# LIC_rack_CV-00.net
KiCad netlist of a schematic drawn in EAGLE
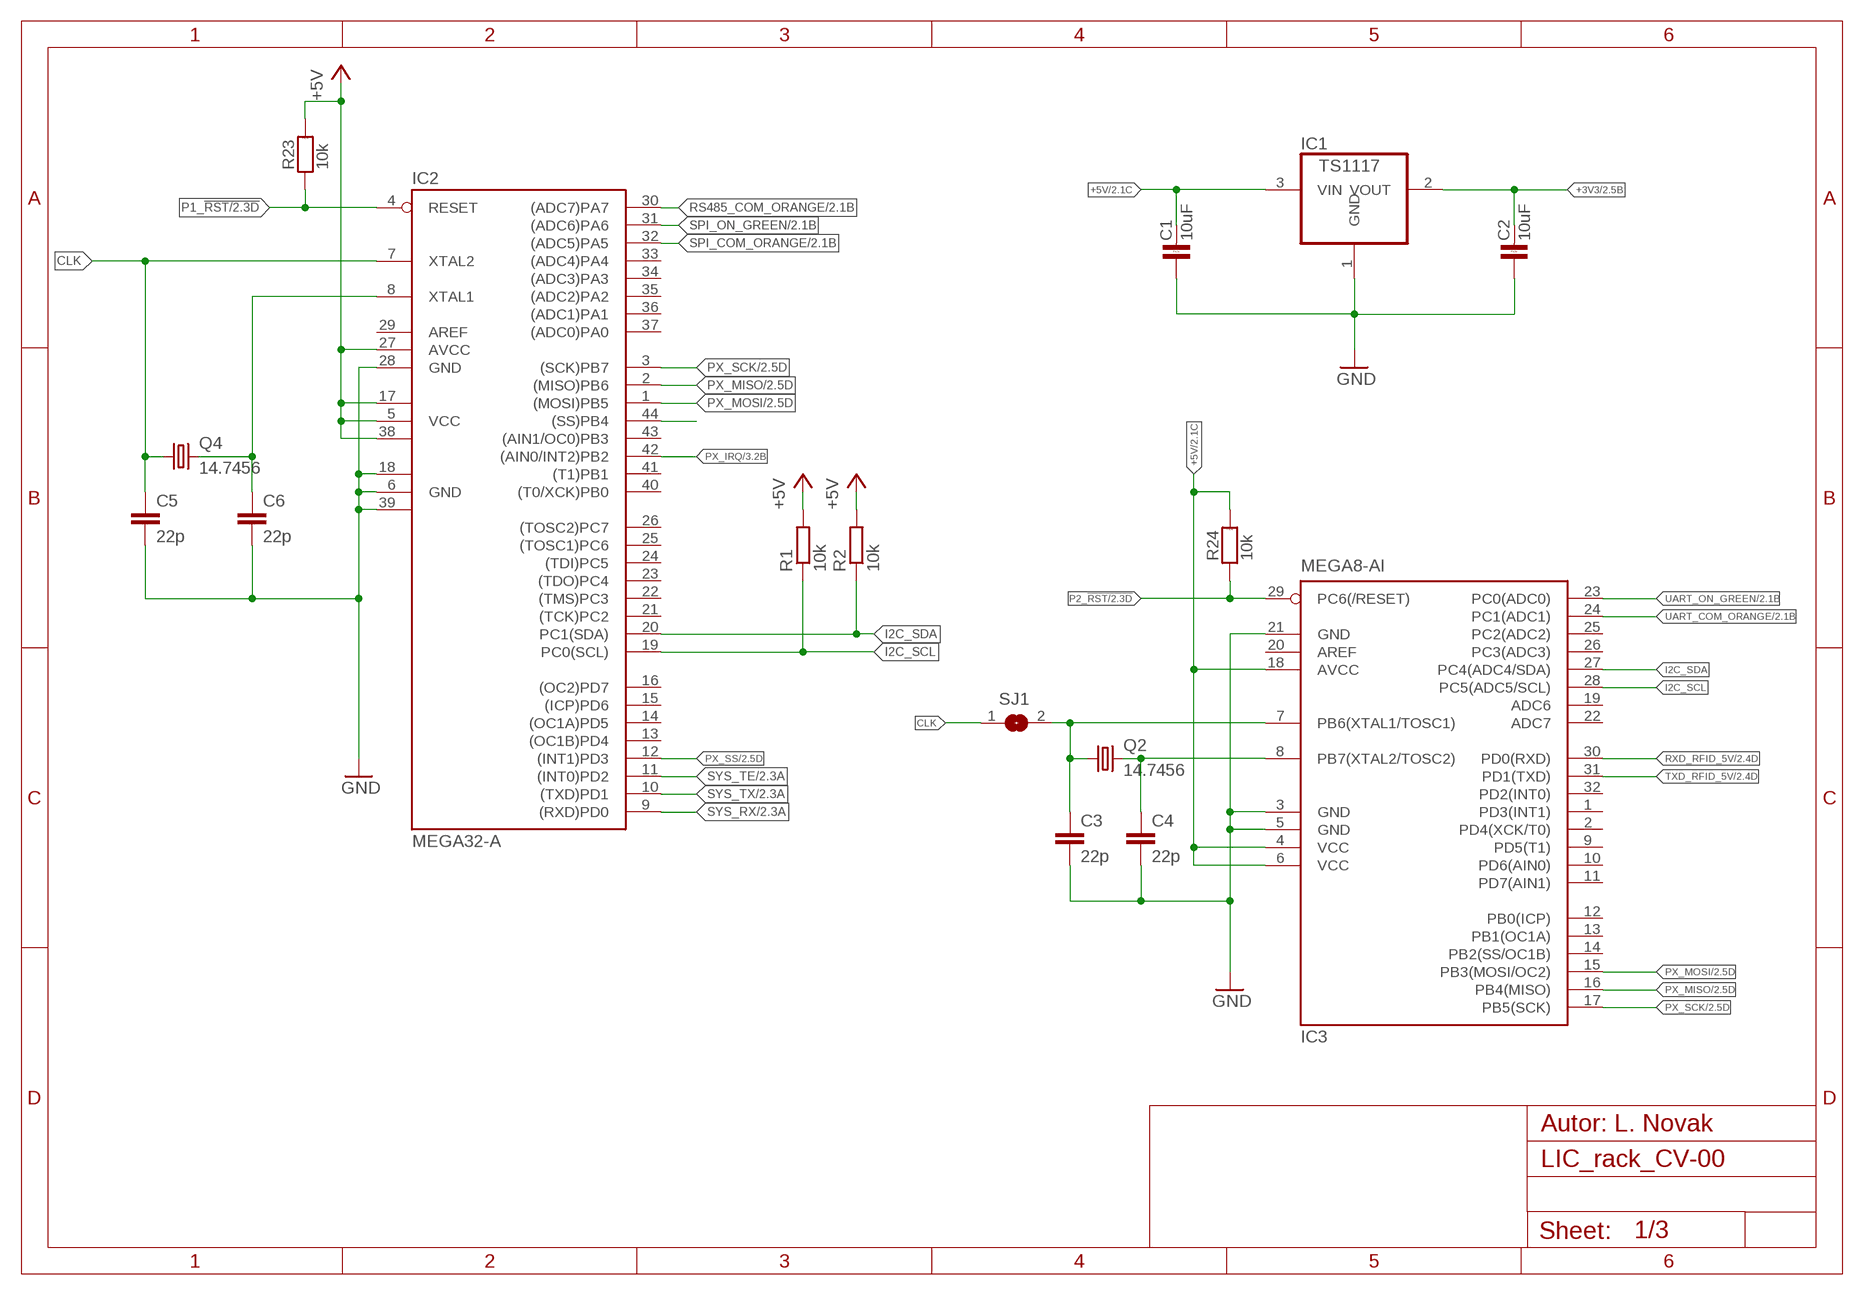
[diagram p0: schematic, sheet 1]
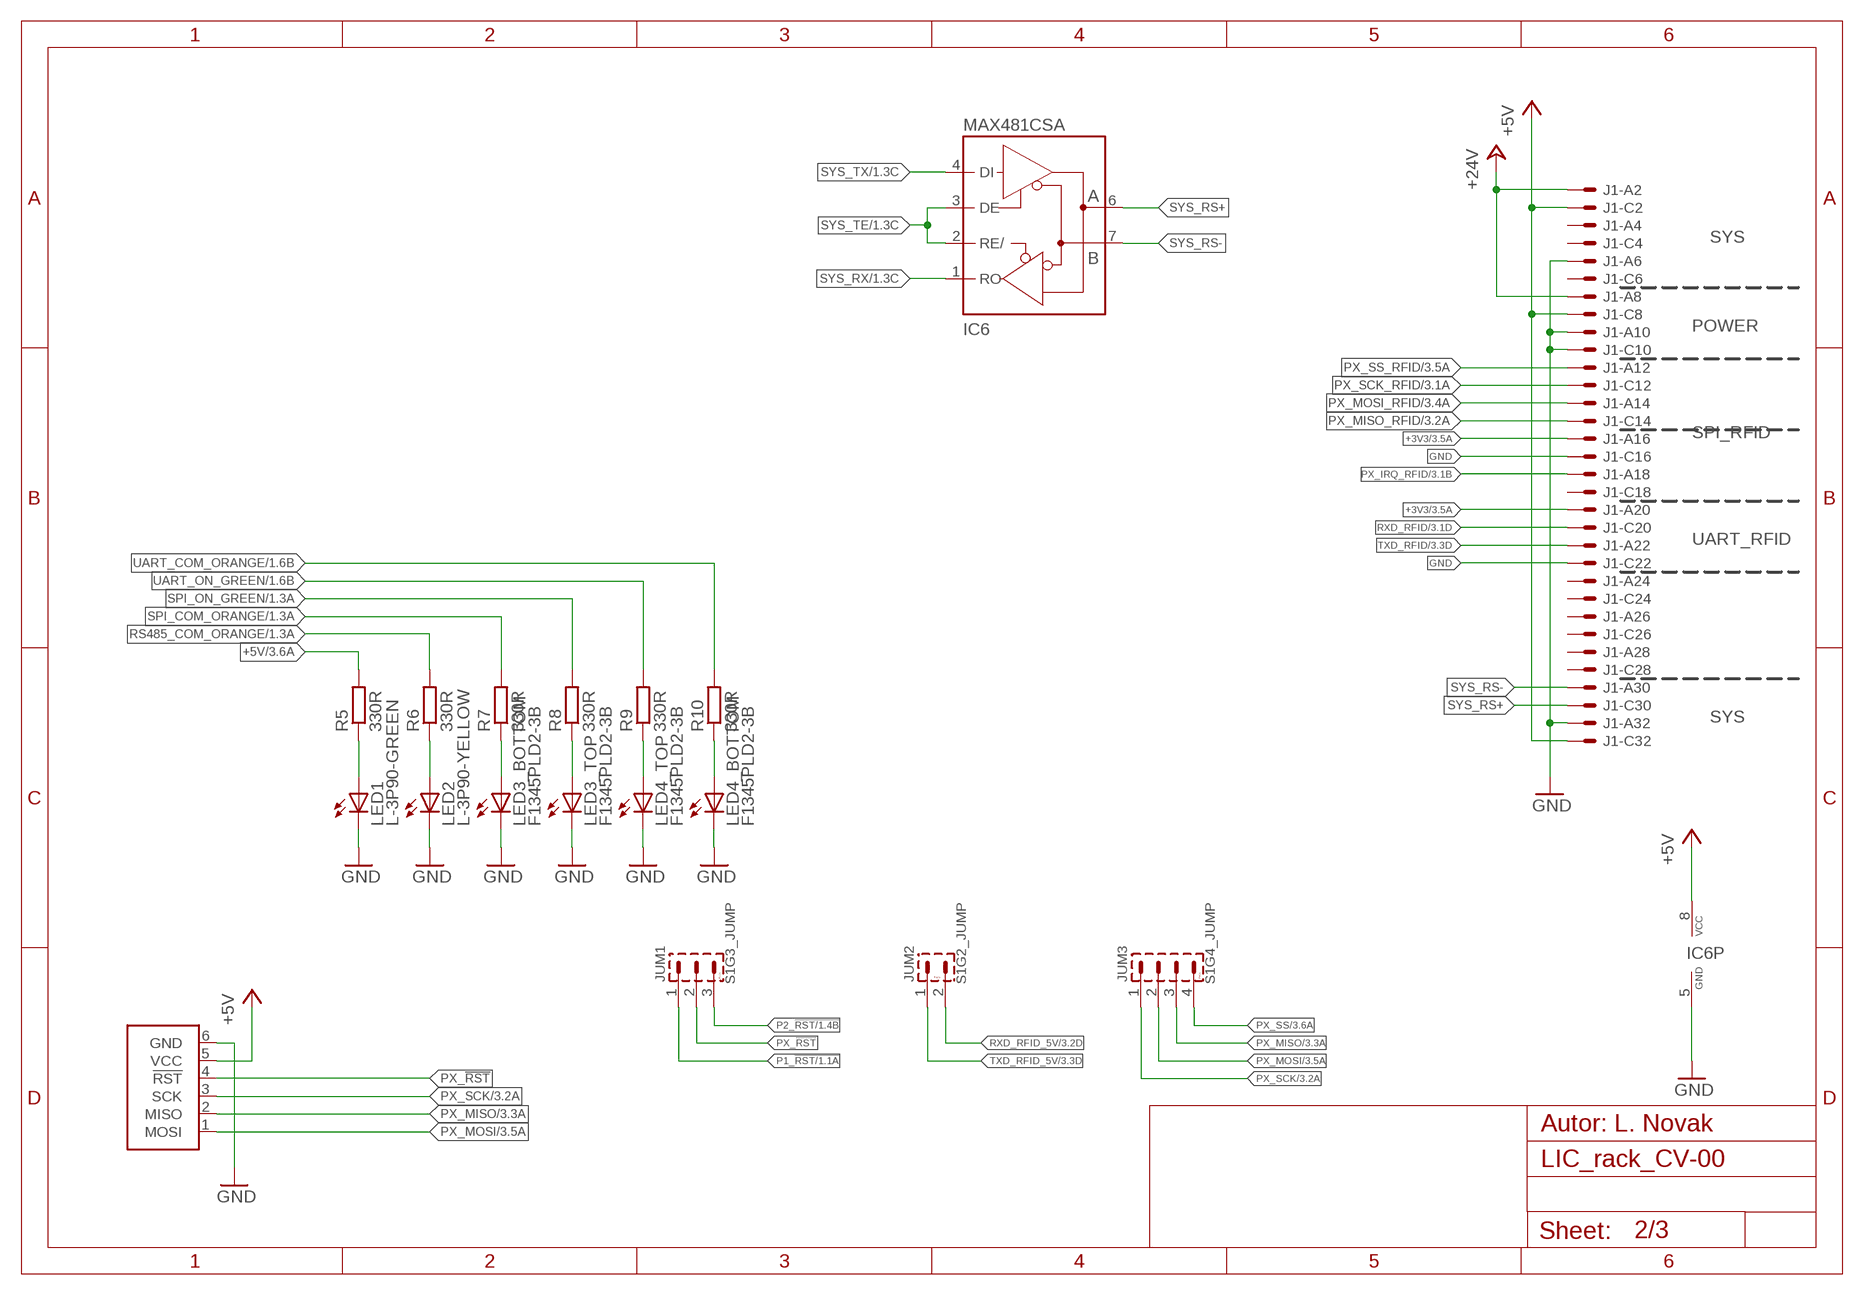
[diagram p1: schematic, sheet 2]
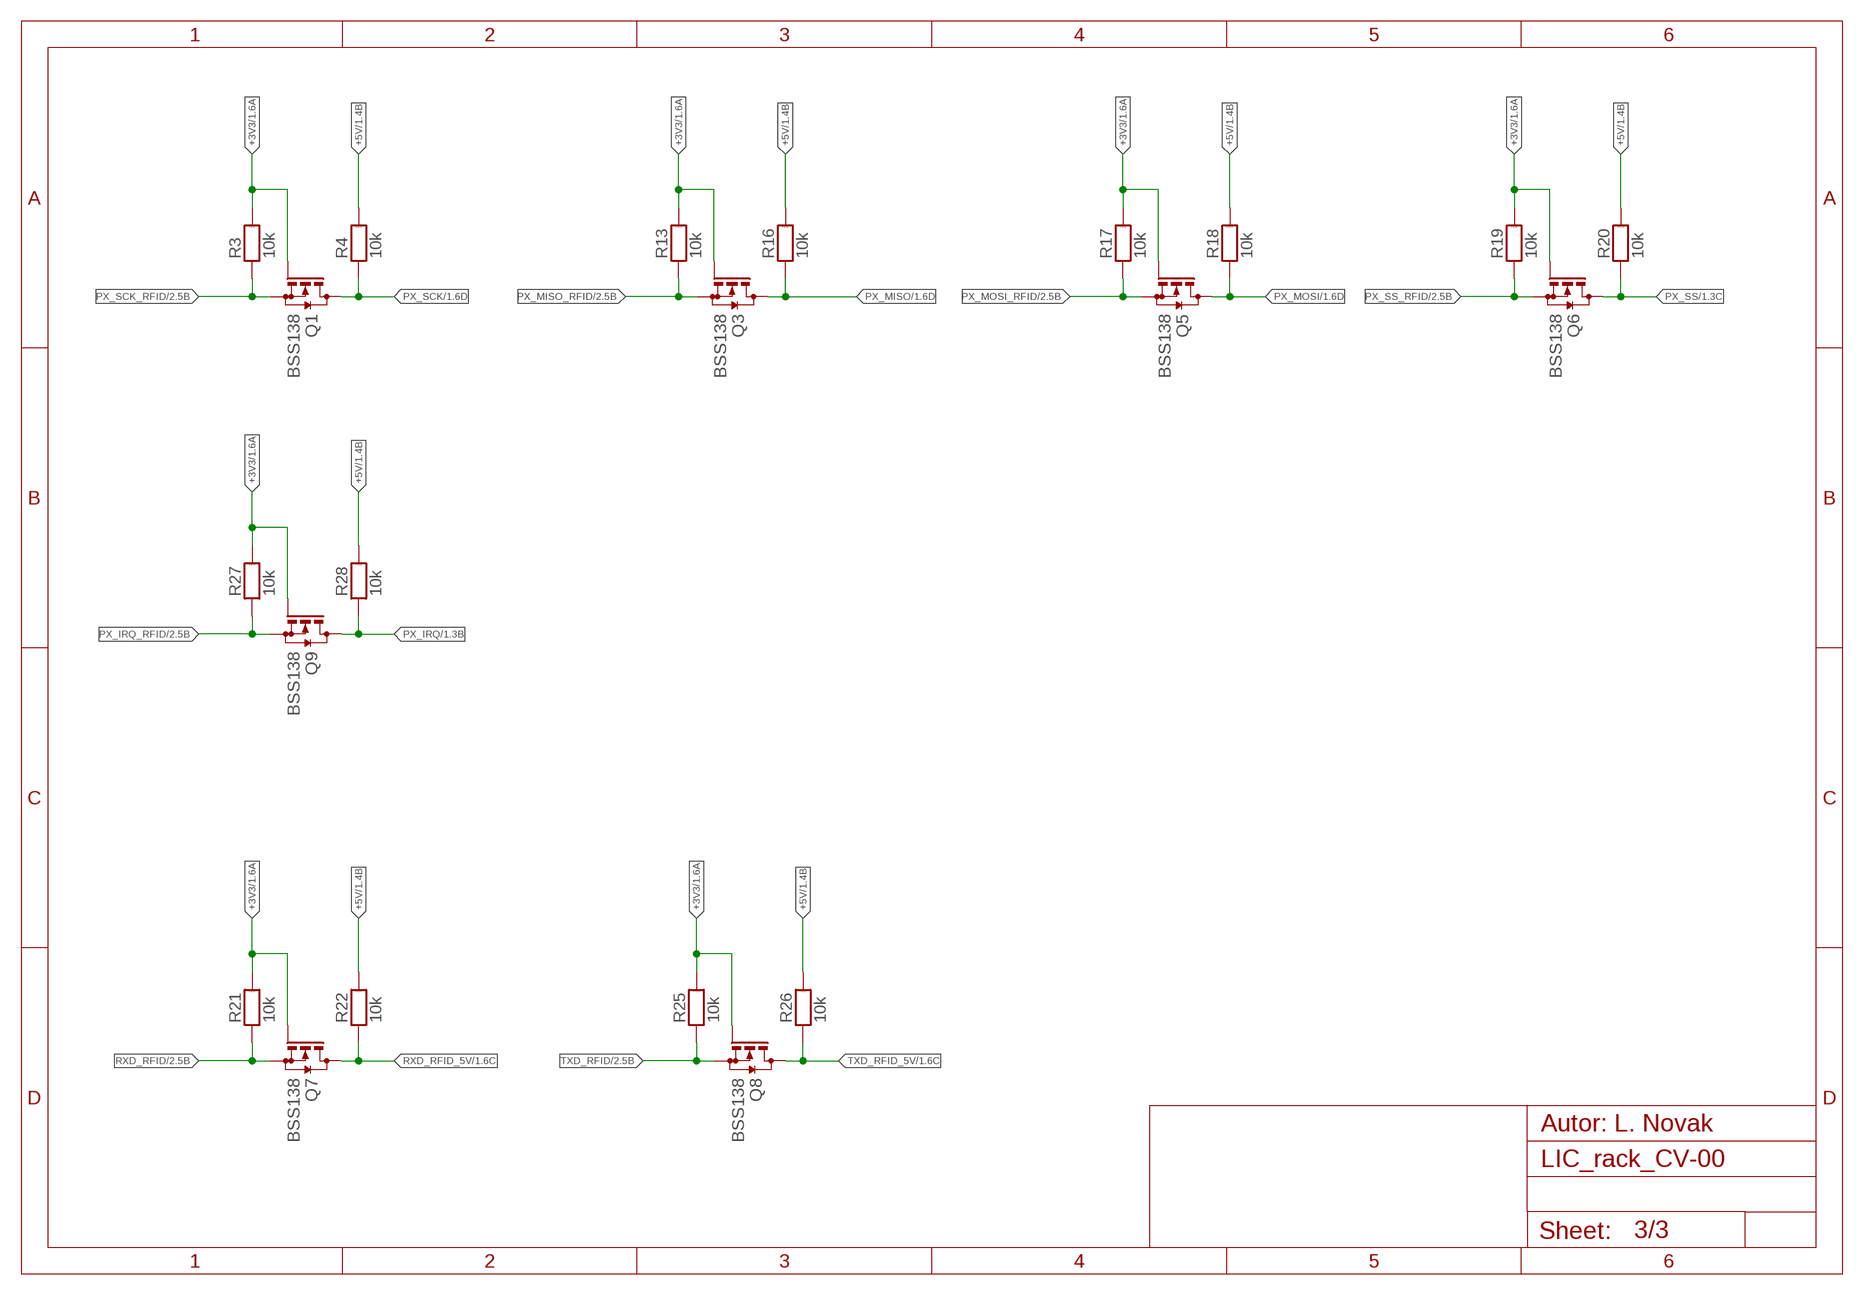
[diagram p2: schematic, sheet 3]

(export (version "E")
  (design (tool "Eeschema 10.0.6"))
  (components
    (comp (ref "IC6")
      (value "MAX481CSA")
      (footprint "eagle-import:SO08")
      (libsource (lib "eagle-import") (part "MAX481CSA"))
    )
    (comp (ref "J1")
      (value "VG32SP")
      (footprint "eagle-import:VG32P")
      (libsource (lib "eagle-import") (part "VG32SP"))
    )
    (comp (ref "JUM1")
      (value "S1G3_JUMP")
      (footprint "eagle-import:S1G3_JUM")
      (libsource (lib "eagle-import") (part "S1G3_JUMP"))
    )
    (comp (ref "JUM2")
      (value "S1G2_JUMP")
      (footprint "eagle-import:S1G2_JUM")
      (libsource (lib "eagle-import") (part "S1G2_JUMP"))
    )
    (comp (ref "JUM3")
      (value "S1G4_JUMP")
      (footprint "eagle-import:S1G4_JUM")
      (libsource (lib "eagle-import") (part "S1G4_JUMP"))
    )
    (comp (ref "LED1")
      (value "L-3P90-GREEN")
      (footprint "eagle-import:L-3P90")
      (libsource (lib "eagle-import") (part "L-3P90-GREEN"))
    )
    (comp (ref "LED2")
      (value "L-3P90-YELLOW")
      (footprint "eagle-import:L-3P90")
      (libsource (lib "eagle-import") (part "L-3P90-YELLOW"))
    )
    (comp (ref "LED3")
      (value "F1345PLD2-3B")
      (footprint "eagle-import:F1345PLD2-3B")
      (libsource (lib "eagle-import") (part "F1345PLD2-3B"))
    )
    (comp (ref "LED4")
      (value "F1345PLD2-3B")
      (footprint "eagle-import:F1345PLD2-3B")
      (libsource (lib "eagle-import") (part "F1345PLD2-3B"))
    )
    (comp (ref "R5")
      (value "330R")
      (footprint "eagle-import:R1206")
      (libsource (lib "eagle-import") (part "R-EU_R1206"))
    )
    (comp (ref "R6")
      (value "330R")
      (footprint "eagle-import:R1206")
      (libsource (lib "eagle-import") (part "R-EU_R1206"))
    )
    (comp (ref "R7")
      (value "330R")
      (footprint "eagle-import:R1206")
      (libsource (lib "eagle-import") (part "R-EU_R1206"))
    )
    (comp (ref "R8")
      (value "330R")
      (footprint "eagle-import:R1206")
      (libsource (lib "eagle-import") (part "R-EU_R1206"))
    )
    (comp (ref "R9")
      (value "330R")
      (footprint "eagle-import:R1206")
      (libsource (lib "eagle-import") (part "R-EU_R1206"))
    )
    (comp (ref "R10")
      (value "330R")
      (footprint "eagle-import:R1206")
      (libsource (lib "eagle-import") (part "R-EU_R1206"))
    )
    (comp (ref "U1")
      (value "ATPROG-V")
      (footprint "eagle-import:6410-06")
      (libsource (lib "eagle-import") (part "ATPROG-V"))
    )
    (comp (ref "Q1")
      (value "BSS138")
      (footprint "eagle-import:SOT23")
      (libsource (lib "eagle-import") (part "BSS123"))
    )
    (comp (ref "Q3")
      (value "BSS138")
      (footprint "eagle-import:SOT23")
      (libsource (lib "eagle-import") (part "BSS123"))
    )
    (comp (ref "Q5")
      (value "BSS138")
      (footprint "eagle-import:SOT23")
      (libsource (lib "eagle-import") (part "BSS123"))
    )
    (comp (ref "Q6")
      (value "BSS138")
      (footprint "eagle-import:SOT23")
      (libsource (lib "eagle-import") (part "BSS123"))
    )
    (comp (ref "Q7")
      (value "BSS138")
      (footprint "eagle-import:SOT23")
      (libsource (lib "eagle-import") (part "BSS123"))
    )
    (comp (ref "Q8")
      (value "BSS138")
      (footprint "eagle-import:SOT23")
      (libsource (lib "eagle-import") (part "BSS123"))
    )
    (comp (ref "Q9")
      (value "BSS138")
      (footprint "eagle-import:SOT23")
      (libsource (lib "eagle-import") (part "BSS123"))
    )
    (comp (ref "R3")
      (value "10k")
      (footprint "eagle-import:1206")
      (libsource (lib "eagle-import") (part "R_1206"))
    )
    (comp (ref "R4")
      (value "10k")
      (footprint "eagle-import:1206")
      (libsource (lib "eagle-import") (part "R_1206"))
    )
    (comp (ref "R13")
      (value "10k")
      (footprint "eagle-import:1206")
      (libsource (lib "eagle-import") (part "R_1206"))
    )
    (comp (ref "R16")
      (value "10k")
      (footprint "eagle-import:1206")
      (libsource (lib "eagle-import") (part "R_1206"))
    )
    (comp (ref "R17")
      (value "10k")
      (footprint "eagle-import:1206")
      (libsource (lib "eagle-import") (part "R_1206"))
    )
    (comp (ref "R18")
      (value "10k")
      (footprint "eagle-import:1206")
      (libsource (lib "eagle-import") (part "R_1206"))
    )
    (comp (ref "R19")
      (value "10k")
      (footprint "eagle-import:1206")
      (libsource (lib "eagle-import") (part "R_1206"))
    )
    (comp (ref "R20")
      (value "10k")
      (footprint "eagle-import:1206")
      (libsource (lib "eagle-import") (part "R_1206"))
    )
    (comp (ref "R21")
      (value "10k")
      (footprint "eagle-import:1206")
      (libsource (lib "eagle-import") (part "R_1206"))
    )
    (comp (ref "R22")
      (value "10k")
      (footprint "eagle-import:1206")
      (libsource (lib "eagle-import") (part "R_1206"))
    )
    (comp (ref "R25")
      (value "10k")
      (footprint "eagle-import:1206")
      (libsource (lib "eagle-import") (part "R_1206"))
    )
    (comp (ref "R26")
      (value "10k")
      (footprint "eagle-import:1206")
      (libsource (lib "eagle-import") (part "R_1206"))
    )
    (comp (ref "R27")
      (value "10k")
      (footprint "eagle-import:1206")
      (libsource (lib "eagle-import") (part "R_1206"))
    )
    (comp (ref "R28")
      (value "10k")
      (footprint "eagle-import:1206")
      (libsource (lib "eagle-import") (part "R_1206"))
    )
    (comp (ref "C1")
      (value "10uF")
      (footprint "eagle-import:1206")
      (libsource (lib "eagle-import") (part "C-KER_1206"))
    )
    (comp (ref "C2")
      (value "10uF")
      (footprint "eagle-import:1206")
      (libsource (lib "eagle-import") (part "C-KER_1206"))
    )
    (comp (ref "C3")
      (value "22p")
      (footprint "eagle-import:C0805")
      (libsource (lib "eagle-import") (part "C-EUC0805"))
    )
    (comp (ref "C4")
      (value "22p")
      (footprint "eagle-import:C0805")
      (libsource (lib "eagle-import") (part "C-EUC0805"))
    )
    (comp (ref "C5")
      (value "22p")
      (footprint "eagle-import:C0805")
      (libsource (lib "eagle-import") (part "C-EUC0805"))
    )
    (comp (ref "C6")
      (value "22p")
      (footprint "eagle-import:C0805")
      (libsource (lib "eagle-import") (part "C-EUC0805"))
    )
    (comp (ref "IC1")
      (value "TS1117")
      (footprint "eagle-import:SOT223")
      (fields (field (name "MPN") "REG1117"))
      (libsource (lib "eagle-import") (part "REG1117"))
    )
    (comp (ref "IC2")
      (value "MEGA32-A")
      (footprint "eagle-import:TQFP44")
      (fields (field (name "MPN") "ATMEGA32-16AU"))
      (libsource (lib "eagle-import") (part "MEGA32-A"))
    )
    (comp (ref "IC3")
      (value "MEGA8-AI")
      (footprint "eagle-import:TQFP32-08")
      (fields (field (name "MPN") "ATMEGA8-16AU"))
      (libsource (lib "eagle-import") (part "MEGA8-AI"))
    )
    (comp (ref "Q2")
      (value "14.7456")
      (footprint "eagle-import:HC49U70")
      (libsource (lib "eagle-import") (part "XTAL"))
    )
    (comp (ref "Q4")
      (value "14.7456")
      (footprint "eagle-import:HC49U70")
      (libsource (lib "eagle-import") (part "XTAL"))
    )
    (comp (ref "R1")
      (value "10k")
      (footprint "eagle-import:R1206")
      (libsource (lib "eagle-import") (part "R-EU_R1206"))
    )
    (comp (ref "R2")
      (value "10k")
      (footprint "eagle-import:R1206")
      (libsource (lib "eagle-import") (part "R-EU_R1206"))
    )
    (comp (ref "R23")
      (value "10k")
      (footprint "eagle-import:1206")
      (libsource (lib "eagle-import") (part "R_1206"))
    )
    (comp (ref "R24")
      (value "10k")
      (footprint "eagle-import:1206")
      (libsource (lib "eagle-import") (part "R_1206"))
    )
    (comp (ref "SJ1") (value "SJ") (footprint "eagle-import:SJ") (libsource (lib "eagle-import") (part "SJ")))
  )
  (nets
    (net (code "1") (name "+3V3") (class "Default")
      (node (ref "C2") (pin "2") (pinfunction "2_2") (pintype "passive"))
      (node (ref "IC1") (pin "2") (pinfunction "VOUT_2") (pintype "output"))
      (node (ref "J1") (pin "A16") (pinfunction "MS_A16") (pintype "passive"))
      (node (ref "J1") (pin "A20") (pinfunction "MS_A20") (pintype "passive"))
      (node (ref "Q1") (pin "1") (pinfunction "G_1") (pintype "passive"))
      (node (ref "Q3") (pin "1") (pinfunction "G_1") (pintype "passive"))
      (node (ref "Q5") (pin "1") (pinfunction "G_1") (pintype "passive"))
      (node (ref "Q6") (pin "1") (pinfunction "G_1") (pintype "passive"))
      (node (ref "Q7") (pin "1") (pinfunction "G_1") (pintype "passive"))
      (node (ref "Q8") (pin "1") (pinfunction "G_1") (pintype "passive"))
      (node (ref "Q9") (pin "1") (pinfunction "G_1") (pintype "passive"))
      (node (ref "R13") (pin "2") (pinfunction "2_2") (pintype "passive"))
      (node (ref "R17") (pin "2") (pinfunction "2_2") (pintype "passive"))
      (node (ref "R19") (pin "2") (pinfunction "2_2") (pintype "passive"))
      (node (ref "R21") (pin "2") (pinfunction "2_2") (pintype "passive"))
      (node (ref "R25") (pin "2") (pinfunction "2_2") (pintype "passive"))
      (node (ref "R27") (pin "2") (pinfunction "2_2") (pintype "passive"))
      (node (ref "R3") (pin "2") (pinfunction "2_2") (pintype "passive"))
    )
    (net (code "2") (name "+5V") (class "Default")
      (node (ref "C1") (pin "2") (pinfunction "2_2") (pintype "passive"))
      (node (ref "IC1") (pin "3") (pinfunction "VIN_3") (pintype "input"))
      (node (ref "IC2") (pin "17") (pinfunction "VCC1_17") (pintype "power_in"))
      (node (ref "IC2") (pin "27") (pinfunction "AVCC_27") (pintype "power_in"))
      (node (ref "IC2") (pin "38") (pinfunction "VCC2_38") (pintype "power_in"))
      (node (ref "IC2") (pin "5") (pinfunction "VCC_5") (pintype "power_in"))
      (node (ref "IC3") (pin "18") (pinfunction "AVCC_18") (pintype "power_in"))
      (node (ref "IC3") (pin "4") (pinfunction "VCC_4") (pintype "power_in"))
      (node (ref "IC3") (pin "6") (pinfunction "VCC_6") (pintype "power_in"))
      (node (ref "IC6") (pin "8") (pinfunction "VCC_8") (pintype "power_in"))
      (node (ref "J1") (pin "C2") (pinfunction "MS_C2") (pintype "passive"))
      (node (ref "J1") (pin "C32") (pinfunction "MSV_C32") (pintype "passive"))
      (node (ref "J1") (pin "C8") (pinfunction "MS_C8") (pintype "passive"))
      (node (ref "R1") (pin "2") (pinfunction "2_2") (pintype "passive"))
      (node (ref "R16") (pin "2") (pinfunction "2_2") (pintype "passive"))
      (node (ref "R18") (pin "2") (pinfunction "2_2") (pintype "passive"))
      (node (ref "R2") (pin "2") (pinfunction "2_2") (pintype "passive"))
      (node (ref "R20") (pin "2") (pinfunction "2_2") (pintype "passive"))
      (node (ref "R22") (pin "2") (pinfunction "2_2") (pintype "passive"))
      (node (ref "R23") (pin "2") (pinfunction "2_2") (pintype "passive"))
      (node (ref "R24") (pin "2") (pinfunction "2_2") (pintype "passive"))
      (node (ref "R26") (pin "2") (pinfunction "2_2") (pintype "passive"))
      (node (ref "R28") (pin "2") (pinfunction "2_2") (pintype "passive"))
      (node (ref "R4") (pin "2") (pinfunction "2_2") (pintype "passive"))
      (node (ref "R5") (pin "2") (pinfunction "2_2") (pintype "passive"))
      (node (ref "U1") (pin "5") (pinfunction "VCC_5") (pintype "power_in"))
    )
    (net (code "3") (name "+24V") (class "Default")
      (node (ref "J1") (pin "A2") (pinfunction "MS_A2") (pintype "passive"))
      (node (ref "J1") (pin "A8") (pinfunction "MS_A8") (pintype "passive"))
    )
    (net (code "4") (name "CLK") (class "Default")
      (node (ref "C5") (pin "1") (pinfunction "1_1") (pintype "passive"))
      (node (ref "IC2") (pin "7") (pinfunction "XTAL2_7") (pintype "bidirectional"))
      (node (ref "Q4") (pin "1") (pinfunction "1_1") (pintype "passive"))
      (node (ref "SJ1") (pin "1") (pinfunction "1_1") (pintype "passive"))
    )
    (net (code "5") (name "GND") (class "Default")
      (node (ref "C1") (pin "1") (pinfunction "1_1") (pintype "passive"))
      (node (ref "C2") (pin "1") (pinfunction "1_1") (pintype "passive"))
      (node (ref "C3") (pin "2") (pinfunction "2_2") (pintype "passive"))
      (node (ref "C4") (pin "2") (pinfunction "2_2") (pintype "passive"))
      (node (ref "C5") (pin "2") (pinfunction "2_2") (pintype "passive"))
      (node (ref "C6") (pin "2") (pinfunction "2_2") (pintype "passive"))
      (node (ref "IC1") (pin "1") (pinfunction "GND_1") (pintype "power_in"))
      (node (ref "IC2") (pin "18") (pinfunction "GND1_18") (pintype "power_in"))
      (node (ref "IC2") (pin "28") (pinfunction "GND_28") (pintype "power_in"))
      (node (ref "IC2") (pin "39") (pinfunction "GND2_39") (pintype "power_in"))
      (node (ref "IC2") (pin "6") (pinfunction "GND_6") (pintype "power_in"))
      (node (ref "IC3") (pin "21") (pinfunction "GND_21") (pintype "power_in"))
      (node (ref "IC3") (pin "3") (pinfunction "GND_3") (pintype "power_in"))
      (node (ref "IC3") (pin "5") (pinfunction "GND_5") (pintype "power_in"))
      (node (ref "IC6") (pin "5") (pinfunction "GND_5") (pintype "power_in"))
      (node (ref "J1") (pin "A10") (pinfunction "MS_A10") (pintype "passive"))
      (node (ref "J1") (pin "A32") (pinfunction "MS_A32") (pintype "passive"))
      (node (ref "J1") (pin "A6") (pinfunction "MS_A6") (pintype "passive"))
      (node (ref "J1") (pin "C10") (pinfunction "MS_C10") (pintype "passive"))
      (node (ref "J1") (pin "C16") (pinfunction "MS_C16") (pintype "passive"))
      (node (ref "J1") (pin "C22") (pinfunction "MS_C22") (pintype "passive"))
      (node (ref "LED1") (pin "K") (pinfunction "C_K") (pintype "passive"))
      (node (ref "LED2") (pin "K") (pinfunction "C_K") (pintype "passive"))
      (node (ref "LED3") (pin "1K") (pinfunction "C_1K") (pintype "passive"))
      (node (ref "LED3") (pin "2K") (pinfunction "C_2K") (pintype "passive"))
      (node (ref "LED4") (pin "1K") (pinfunction "C_1K") (pintype "passive"))
      (node (ref "LED4") (pin "2K") (pinfunction "C_2K") (pintype "passive"))
      (node (ref "U1") (pin "6") (pinfunction "GND_6") (pintype "power_in"))
    )
    (net (code "6") (name "I2C_SCL") (class "Default")
      (node (ref "IC2") (pin "19") (pinfunction "PC0(SCL)_19") (pintype "bidirectional"))
      (node (ref "IC3") (pin "28") (pinfunction "PC5(ADC5/SCL)_28") (pintype "bidirectional"))
      (node (ref "R1") (pin "1") (pinfunction "1_1") (pintype "passive"))
    )
    (net (code "7") (name "I2C_SDA") (class "Default")
      (node (ref "IC2") (pin "20") (pinfunction "PC1(SDA)_20") (pintype "bidirectional"))
      (node (ref "IC3") (pin "27") (pinfunction "PC4(ADC4/SDA)_27") (pintype "bidirectional"))
      (node (ref "R2") (pin "1") (pinfunction "1_1") (pintype "passive"))
    )
    (net (code "8") (name "Net-(IC2-XTAL1)") (class "Default")
      (node (ref "C6") (pin "1") (pinfunction "1_1") (pintype "passive"))
      (node (ref "IC2") (pin "8") (pinfunction "XTAL1_8") (pintype "bidirectional"))
      (node (ref "Q4") (pin "2") (pinfunction "2_2") (pintype "passive"))
    )
    (net (code "9") (name "Net-(IC3-PB6(XTAL1{slash}TOSC1))") (class "Default")
      (node (ref "C3") (pin "1") (pinfunction "1_1") (pintype "passive"))
      (node (ref "IC3") (pin "7") (pinfunction "PB6(XTAL1/TOSC1)_7") (pintype "bidirectional"))
      (node (ref "Q2") (pin "1") (pinfunction "1_1") (pintype "passive"))
      (node (ref "SJ1") (pin "2") (pinfunction "2_2") (pintype "passive"))
    )
    (net (code "10") (name "Net-(IC3-PB7(XTAL2{slash}TOSC2))") (class "Default")
      (node (ref "C4") (pin "1") (pinfunction "1_1") (pintype "passive"))
      (node (ref "IC3") (pin "8") (pinfunction "PB7(XTAL2/TOSC2)_8") (pintype "bidirectional"))
      (node (ref "Q2") (pin "2") (pinfunction "2_2") (pintype "passive"))
    )
    (net (code "11") (name "Net-(LED1-PadA)") (class "Default")
      (node (ref "LED1") (pin "A") (pinfunction "A_A") (pintype "passive"))
      (node (ref "R5") (pin "1") (pinfunction "1_1") (pintype "passive"))
    )
    (net (code "12") (name "Net-(LED2-PadA)") (class "Default")
      (node (ref "LED2") (pin "A") (pinfunction "A_A") (pintype "passive"))
      (node (ref "R6") (pin "1") (pinfunction "1_1") (pintype "passive"))
    )
    (net (code "13") (name "Net-(LED3A-A)") (class "Default")
      (node (ref "LED3") (pin "1A") (pinfunction "A_1A") (pintype "passive"))
      (node (ref "R7") (pin "1") (pinfunction "1_1") (pintype "passive"))
    )
    (net (code "14") (name "Net-(LED3B-A)") (class "Default")
      (node (ref "LED3") (pin "2A") (pinfunction "A_2A") (pintype "passive"))
      (node (ref "R8") (pin "1") (pinfunction "1_1") (pintype "passive"))
    )
    (net (code "15") (name "Net-(LED4A-A)") (class "Default")
      (node (ref "LED4") (pin "1A") (pinfunction "A_1A") (pintype "passive"))
      (node (ref "R10") (pin "1") (pinfunction "1_1") (pintype "passive"))
    )
    (net (code "16") (name "Net-(LED4B-A)") (class "Default")
      (node (ref "LED4") (pin "2A") (pinfunction "A_2A") (pintype "passive"))
      (node (ref "R9") (pin "1") (pinfunction "1_1") (pintype "passive"))
    )
    (net (code "17") (name "P1_~{RST}") (class "Default")
      (node (ref "IC2") (pin "4") (pinfunction "RESET_4") (pintype "input"))
      (node (ref "JUM1") (pin "1") (pinfunction "1_1") (pintype "passive"))
      (node (ref "R23") (pin "1") (pinfunction "1_1") (pintype "passive"))
    )
    (net (code "18") (name "P2_~{RST}") (class "Default")
      (node (ref "IC3") (pin "29") (pinfunction "PC6(/RESET)_29") (pintype "bidirectional"))
      (node (ref "JUM1") (pin "3") (pinfunction "3_3") (pintype "passive"))
      (node (ref "R24") (pin "1") (pinfunction "1_1") (pintype "passive"))
    )
    (net (code "19") (name "PX_IRQ") (class "Default")
      (node (ref "IC2") (pin "42") (pinfunction "(AIN0/INT2)PB2_42") (pintype "bidirectional"))
      (node (ref "Q9") (pin "3") (pinfunction "D_3") (pintype "passive"))
      (node (ref "R28") (pin "1") (pinfunction "1_1") (pintype "passive"))
    )
    (net (code "20") (name "PX_IRQ_RFID") (class "Default")
      (node (ref "J1") (pin "A18") (pinfunction "MS_A18") (pintype "passive"))
      (node (ref "Q9") (pin "2") (pinfunction "S_2") (pintype "passive"))
      (node (ref "R27") (pin "1") (pinfunction "1_1") (pintype "passive"))
    )
    (net (code "21") (name "PX_MISO") (class "Default")
      (node (ref "IC2") (pin "2") (pinfunction "(MISO)PB6_2") (pintype "bidirectional"))
      (node (ref "IC3") (pin "16") (pinfunction "PB4(MISO)_16") (pintype "bidirectional"))
      (node (ref "JUM3") (pin "3") (pinfunction "3_3") (pintype "passive"))
      (node (ref "Q3") (pin "3") (pinfunction "D_3") (pintype "passive"))
      (node (ref "R16") (pin "1") (pinfunction "1_1") (pintype "passive"))
      (node (ref "U1") (pin "2") (pinfunction "MISO_2") (pintype "input"))
    )
    (net (code "22") (name "PX_MISO_RFID") (class "Default")
      (node (ref "J1") (pin "C14") (pinfunction "MS_C14") (pintype "passive"))
      (node (ref "Q3") (pin "2") (pinfunction "S_2") (pintype "passive"))
      (node (ref "R13") (pin "1") (pinfunction "1_1") (pintype "passive"))
    )
    (net (code "23") (name "PX_MOSI") (class "Default")
      (node (ref "IC2") (pin "1") (pinfunction "(MOSI)PB5_1") (pintype "bidirectional"))
      (node (ref "IC3") (pin "15") (pinfunction "PB3(MOSI/OC2)_15") (pintype "bidirectional"))
      (node (ref "JUM3") (pin "2") (pinfunction "2_2") (pintype "passive"))
      (node (ref "Q5") (pin "3") (pinfunction "D_3") (pintype "passive"))
      (node (ref "R18") (pin "1") (pinfunction "1_1") (pintype "passive"))
      (node (ref "U1") (pin "1") (pinfunction "MOSI_1") (pintype "output"))
    )
    (net (code "24") (name "PX_MOSI_RFID") (class "Default")
      (node (ref "J1") (pin "A14") (pinfunction "MS_A14") (pintype "passive"))
      (node (ref "Q5") (pin "2") (pinfunction "S_2") (pintype "passive"))
      (node (ref "R17") (pin "1") (pinfunction "1_1") (pintype "passive"))
    )
    (net (code "25") (name "PX_SCK") (class "Default")
      (node (ref "IC2") (pin "3") (pinfunction "(SCK)PB7_3") (pintype "bidirectional"))
      (node (ref "IC3") (pin "17") (pinfunction "PB5(SCK)_17") (pintype "bidirectional"))
      (node (ref "JUM3") (pin "1") (pinfunction "1_1") (pintype "passive"))
      (node (ref "Q1") (pin "3") (pinfunction "D_3") (pintype "passive"))
      (node (ref "R4") (pin "1") (pinfunction "1_1") (pintype "passive"))
      (node (ref "U1") (pin "3") (pinfunction "SCK_3") (pintype "input"))
    )
    (net (code "26") (name "PX_SCK_RFID") (class "Default")
      (node (ref "J1") (pin "C12") (pinfunction "MS_C12") (pintype "passive"))
      (node (ref "Q1") (pin "2") (pinfunction "S_2") (pintype "passive"))
      (node (ref "R3") (pin "1") (pinfunction "1_1") (pintype "passive"))
    )
    (net (code "27") (name "PX_SS") (class "Default")
      (node (ref "IC2") (pin "12") (pinfunction "(INT1)PD3_12") (pintype "bidirectional"))
      (node (ref "JUM3") (pin "4") (pinfunction "4_4") (pintype "passive"))
      (node (ref "Q6") (pin "3") (pinfunction "D_3") (pintype "passive"))
      (node (ref "R20") (pin "1") (pinfunction "1_1") (pintype "passive"))
    )
    (net (code "28") (name "PX_SS_RFID") (class "Default")
      (node (ref "J1") (pin "A12") (pinfunction "MS_A12") (pintype "passive"))
      (node (ref "Q6") (pin "2") (pinfunction "S_2") (pintype "passive"))
      (node (ref "R19") (pin "1") (pinfunction "1_1") (pintype "passive"))
    )
    (net (code "29") (name "PX_~{RST}") (class "Default")
      (node (ref "JUM1") (pin "2") (pinfunction "2_2") (pintype "passive"))
      (node (ref "U1") (pin "4") (pinfunction "~{RST}_4") (pintype "input"))
    )
    (net (code "30") (name "RS485_COM_ORANGE") (class "Default")
      (node (ref "IC2") (pin "30") (pinfunction "(ADC7)PA7_30") (pintype "bidirectional"))
      (node (ref "R6") (pin "2") (pinfunction "2_2") (pintype "passive"))
    )
    (net (code "31") (name "RXD_RFID") (class "Default")
      (node (ref "J1") (pin "C20") (pinfunction "MS_C20") (pintype "passive"))
      (node (ref "Q7") (pin "2") (pinfunction "S_2") (pintype "passive"))
      (node (ref "R21") (pin "1") (pinfunction "1_1") (pintype "passive"))
    )
    (net (code "32") (name "RXD_RFID_5V") (class "Default")
      (node (ref "IC3") (pin "30") (pinfunction "PD0(RXD)_30") (pintype "bidirectional"))
      (node (ref "JUM2") (pin "2") (pinfunction "2_2") (pintype "passive"))
      (node (ref "Q7") (pin "3") (pinfunction "D_3") (pintype "passive"))
      (node (ref "R22") (pin "1") (pinfunction "1_1") (pintype "passive"))
    )
    (net (code "33") (name "SPI_COM_ORANGE") (class "Default")
      (node (ref "IC2") (pin "32") (pinfunction "(ADC5)PA5_32") (pintype "bidirectional"))
      (node (ref "R7") (pin "2") (pinfunction "2_2") (pintype "passive"))
    )
    (net (code "34") (name "SPI_ON_GREEN") (class "Default")
      (node (ref "IC2") (pin "31") (pinfunction "(ADC6)PA6_31") (pintype "bidirectional"))
      (node (ref "R8") (pin "2") (pinfunction "2_2") (pintype "passive"))
    )
    (net (code "35") (name "SYS_RS+") (class "Default")
      (node (ref "IC6") (pin "6") (pinfunction "A_6") (pintype "passive"))
      (node (ref "J1") (pin "C30") (pinfunction "MS_C30") (pintype "passive"))
    )
    (net (code "36") (name "SYS_RS-") (class "Default")
      (node (ref "IC6") (pin "7") (pinfunction "B_7") (pintype "passive"))
      (node (ref "J1") (pin "A30") (pinfunction "MS_A30") (pintype "passive"))
    )
    (net (code "37") (name "SYS_RX") (class "Default")
      (node (ref "IC2") (pin "9") (pinfunction "(RXD)PD0_9") (pintype "bidirectional"))
      (node (ref "IC6") (pin "1") (pinfunction "RO_1") (pintype "output"))
    )
    (net (code "38") (name "SYS_TE") (class "Default")
      (node (ref "IC2") (pin "11") (pinfunction "(INT0)PD2_11") (pintype "bidirectional"))
      (node (ref "IC6") (pin "2") (pinfunction "RE/_2") (pintype "input"))
      (node (ref "IC6") (pin "3") (pinfunction "DE_3") (pintype "input"))
    )
    (net (code "39") (name "SYS_TX") (class "Default")
      (node (ref "IC2") (pin "10") (pinfunction "(TXD)PD1_10") (pintype "bidirectional"))
      (node (ref "IC6") (pin "4") (pinfunction "DI_4") (pintype "input"))
    )
    (net (code "40") (name "TXD_RFID") (class "Default")
      (node (ref "J1") (pin "A22") (pinfunction "MS_A22") (pintype "passive"))
      (node (ref "Q8") (pin "2") (pinfunction "S_2") (pintype "passive"))
      (node (ref "R25") (pin "1") (pinfunction "1_1") (pintype "passive"))
    )
    (net (code "41") (name "TXD_RFID_5V") (class "Default")
      (node (ref "IC3") (pin "31") (pinfunction "PD1(TXD)_31") (pintype "bidirectional"))
      (node (ref "JUM2") (pin "1") (pinfunction "1_1") (pintype "passive"))
      (node (ref "Q8") (pin "3") (pinfunction "D_3") (pintype "passive"))
      (node (ref "R26") (pin "1") (pinfunction "1_1") (pintype "passive"))
    )
    (net (code "42") (name "UART_COM_ORANGE") (class "Default")
      (node (ref "IC3") (pin "24") (pinfunction "PC1(ADC1)_24") (pintype "bidirectional"))
      (node (ref "R10") (pin "2") (pinfunction "2_2") (pintype "passive"))
    )
    (net (code "43") (name "UART_ON_GREEN") (class "Default")
      (node (ref "IC3") (pin "23") (pinfunction "PC0(ADC0)_23") (pintype "bidirectional"))
      (node (ref "R9") (pin "2") (pinfunction "2_2") (pintype "passive"))
    )
    (net (code "44") (name "unconnected-(IC2-(ADC0)PA0-Pad37)") (class "Default")
      (node (ref "IC2") (pin "37") (pinfunction "(ADC0)PA0_37") (pintype "bidirectional"))
    )
    (net (code "45") (name "unconnected-(IC2-(ADC1)PA1-Pad36)") (class "Default")
      (node (ref "IC2") (pin "36") (pinfunction "(ADC1)PA1_36") (pintype "bidirectional"))
    )
    (net (code "46") (name "unconnected-(IC2-(ADC2)PA2-Pad35)") (class "Default")
      (node (ref "IC2") (pin "35") (pinfunction "(ADC2)PA2_35") (pintype "bidirectional"))
    )
    (net (code "47") (name "unconnected-(IC2-(ADC3)PA3-Pad34)") (class "Default")
      (node (ref "IC2") (pin "34") (pinfunction "(ADC3)PA3_34") (pintype "bidirectional"))
    )
    (net (code "48") (name "unconnected-(IC2-(ADC4)PA4-Pad33)") (class "Default")
      (node (ref "IC2") (pin "33") (pinfunction "(ADC4)PA4_33") (pintype "bidirectional"))
    )
    (net (code "49") (name "unconnected-(IC2-(AIN1{slash}OC0)PB3-Pad43)") (class "Default")
      (node (ref "IC2") (pin "43") (pinfunction "(AIN1/OC0)PB3_43") (pintype "bidirectional"))
    )
    (net (code "50") (name "unconnected-(IC2-(ICP)PD6-Pad15)") (class "Default")
      (node (ref "IC2") (pin "15") (pinfunction "(ICP)PD6_15") (pintype "bidirectional"))
    )
    (net (code "51") (name "unconnected-(IC2-(OC1A)PD5-Pad14)") (class "Default")
      (node (ref "IC2") (pin "14") (pinfunction "(OC1A)PD5_14") (pintype "bidirectional"))
    )
    (net (code "52") (name "unconnected-(IC2-(OC1B)PD4-Pad13)") (class "Default")
      (node (ref "IC2") (pin "13") (pinfunction "(OC1B)PD4_13") (pintype "bidirectional"))
    )
    (net (code "53") (name "unconnected-(IC2-(OC2)PD7-Pad16)") (class "Default")
      (node (ref "IC2") (pin "16") (pinfunction "(OC2)PD7_16") (pintype "bidirectional"))
    )
    (net (code "54") (name "unconnected-(IC2-(SS)PB4-Pad44)") (class "Default")
      (node (ref "IC2") (pin "44") (pinfunction "(SS)PB4_44") (pintype "bidirectional"))
    )
    (net (code "55") (name "unconnected-(IC2-(T0{slash}XCK)PB0-Pad40)") (class "Default")
      (node (ref "IC2") (pin "40") (pinfunction "(T0/XCK)PB0_40") (pintype "bidirectional"))
    )
    (net (code "56") (name "unconnected-(IC2-(T1)PB1-Pad41)") (class "Default")
      (node (ref "IC2") (pin "41") (pinfunction "(T1)PB1_41") (pintype "bidirectional"))
    )
    (net (code "57") (name "unconnected-(IC2-(TCK)PC2-Pad21)") (class "Default")
      (node (ref "IC2") (pin "21") (pinfunction "(TCK)PC2_21") (pintype "bidirectional"))
    )
    (net (code "58") (name "unconnected-(IC2-(TDI)PC5-Pad24)") (class "Default")
      (node (ref "IC2") (pin "24") (pinfunction "(TDI)PC5_24") (pintype "bidirectional"))
    )
    (net (code "59") (name "unconnected-(IC2-(TDO)PC4-Pad23)") (class "Default")
      (node (ref "IC2") (pin "23") (pinfunction "(TDO)PC4_23") (pintype "bidirectional"))
    )
    (net (code "60") (name "unconnected-(IC2-(TMS)PC3-Pad22)") (class "Default")
      (node (ref "IC2") (pin "22") (pinfunction "(TMS)PC3_22") (pintype "bidirectional"))
    )
    (net (code "61") (name "unconnected-(IC2-(TOSC1)PC6-Pad25)") (class "Default")
      (node (ref "IC2") (pin "25") (pinfunction "(TOSC1)PC6_25") (pintype "bidirectional"))
    )
    (net (code "62") (name "unconnected-(IC2-(TOSC2)PC7-Pad26)") (class "Default")
      (node (ref "IC2") (pin "26") (pinfunction "(TOSC2)PC7_26") (pintype "bidirectional"))
    )
    (net (code "63") (name "unconnected-(IC2-AREF-Pad29)") (class "Default")
      (node (ref "IC2") (pin "29") (pinfunction "AREF_29") (pintype "passive"))
    )
    (net (code "64") (name "unconnected-(IC3-ADC6-Pad19)") (class "Default")
      (node (ref "IC3") (pin "19") (pinfunction "ADC6_19") (pintype "bidirectional"))
    )
    (net (code "65") (name "unconnected-(IC3-ADC7-Pad22)") (class "Default")
      (node (ref "IC3") (pin "22") (pinfunction "ADC7_22") (pintype "bidirectional"))
    )
    (net (code "66") (name "unconnected-(IC3-AREF-Pad20)") (class "Default")
      (node (ref "IC3") (pin "20") (pinfunction "AREF_20") (pintype "passive"))
    )
    (net (code "67") (name "unconnected-(IC3-PB0(ICP)-Pad12)") (class "Default")
      (node (ref "IC3") (pin "12") (pinfunction "PB0(ICP)_12") (pintype "bidirectional"))
    )
    (net (code "68") (name "unconnected-(IC3-PB1(OC1A)-Pad13)") (class "Default")
      (node (ref "IC3") (pin "13") (pinfunction "PB1(OC1A)_13") (pintype "bidirectional"))
    )
    (net (code "69") (name "unconnected-(IC3-PB2(SS{slash}OC1B)-Pad14)") (class "Default")
      (node (ref "IC3") (pin "14") (pinfunction "PB2(SS/OC1B)_14") (pintype "bidirectional"))
    )
    (net (code "70") (name "unconnected-(IC3-PC2(ADC2)-Pad25)") (class "Default")
      (node (ref "IC3") (pin "25") (pinfunction "PC2(ADC2)_25") (pintype "bidirectional"))
    )
    (net (code "71") (name "unconnected-(IC3-PC3(ADC3)-Pad26)") (class "Default")
      (node (ref "IC3") (pin "26") (pinfunction "PC3(ADC3)_26") (pintype "bidirectional"))
    )
    (net (code "72") (name "unconnected-(IC3-PD2(INT0)-Pad32)") (class "Default")
      (node (ref "IC3") (pin "32") (pinfunction "PD2(INT0)_32") (pintype "bidirectional"))
    )
    (net (code "73") (name "unconnected-(IC3-PD3(INT1)-Pad1)") (class "Default")
      (node (ref "IC3") (pin "1") (pinfunction "PD3(INT1)_1") (pintype "bidirectional"))
    )
    (net (code "74") (name "unconnected-(IC3-PD4(XCK{slash}T0)-Pad2)") (class "Default")
      (node (ref "IC3") (pin "2") (pinfunction "PD4(XCK/T0)_2") (pintype "bidirectional"))
    )
    (net (code "75") (name "unconnected-(IC3-PD5(T1)-Pad9)") (class "Default")
      (node (ref "IC3") (pin "9") (pinfunction "PD5(T1)_9") (pintype "bidirectional"))
    )
    (net (code "76") (name "unconnected-(IC3-PD6(AIN0)-Pad10)") (class "Default")
      (node (ref "IC3") (pin "10") (pinfunction "PD6(AIN0)_10") (pintype "bidirectional"))
    )
    (net (code "77") (name "unconnected-(IC3-PD7(AIN1)-Pad11)") (class "Default")
      (node (ref "IC3") (pin "11") (pinfunction "PD7(AIN1)_11") (pintype "bidirectional"))
    )
    (net (code "78") (name "unconnected-(J1AA-MS-PadC28)") (class "Default")
      (node (ref "J1") (pin "C28") (pinfunction "MS_C28") (pintype "passive"))
    )
    (net (code "79") (name "unconnected-(J1AD-MS-PadC4)") (class "Default")
      (node (ref "J1") (pin "C4") (pinfunction "MS_C4") (pintype "passive"))
    )
    (net (code "80") (name "unconnected-(J1AE-MS-PadC6)") (class "Default")
      (node (ref "J1") (pin "C6") (pinfunction "MS_C6") (pintype "passive"))
    )
    (net (code "81") (name "unconnected-(J1I-MS-PadA24)") (class "Default")
      (node (ref "J1") (pin "A24") (pinfunction "MS_A24") (pintype "passive"))
    )
    (net (code "82") (name "unconnected-(J1J-MS-PadA26)") (class "Default")
      (node (ref "J1") (pin "A26") (pinfunction "MS_A26") (pintype "passive"))
    )
    (net (code "83") (name "unconnected-(J1K-MS-PadA28)") (class "Default")
      (node (ref "J1") (pin "A28") (pinfunction "MS_A28") (pintype "passive"))
    )
    (net (code "84") (name "unconnected-(J1N-MS-PadA4)") (class "Default")
      (node (ref "J1") (pin "A4") (pinfunction "MS_A4") (pintype "passive"))
    )
    (net (code "85") (name "unconnected-(J1U-MS-PadC18)") (class "Default")
      (node (ref "J1") (pin "C18") (pinfunction "MS_C18") (pintype "passive"))
    )
    (net (code "86") (name "unconnected-(J1Y-MS-PadC24)") (class "Default")
      (node (ref "J1") (pin "C24") (pinfunction "MS_C24") (pintype "passive"))
    )
    (net (code "87") (name "unconnected-(J1Z-MS-PadC26)") (class "Default")
      (node (ref "J1") (pin "C26") (pinfunction "MS_C26") (pintype "passive"))
    )
  )
)
